# LB_BIT_oX_1IN_1OUT-XL-v03_1_1x.net
KiCad netlist of a schematic drawn in EAGLE
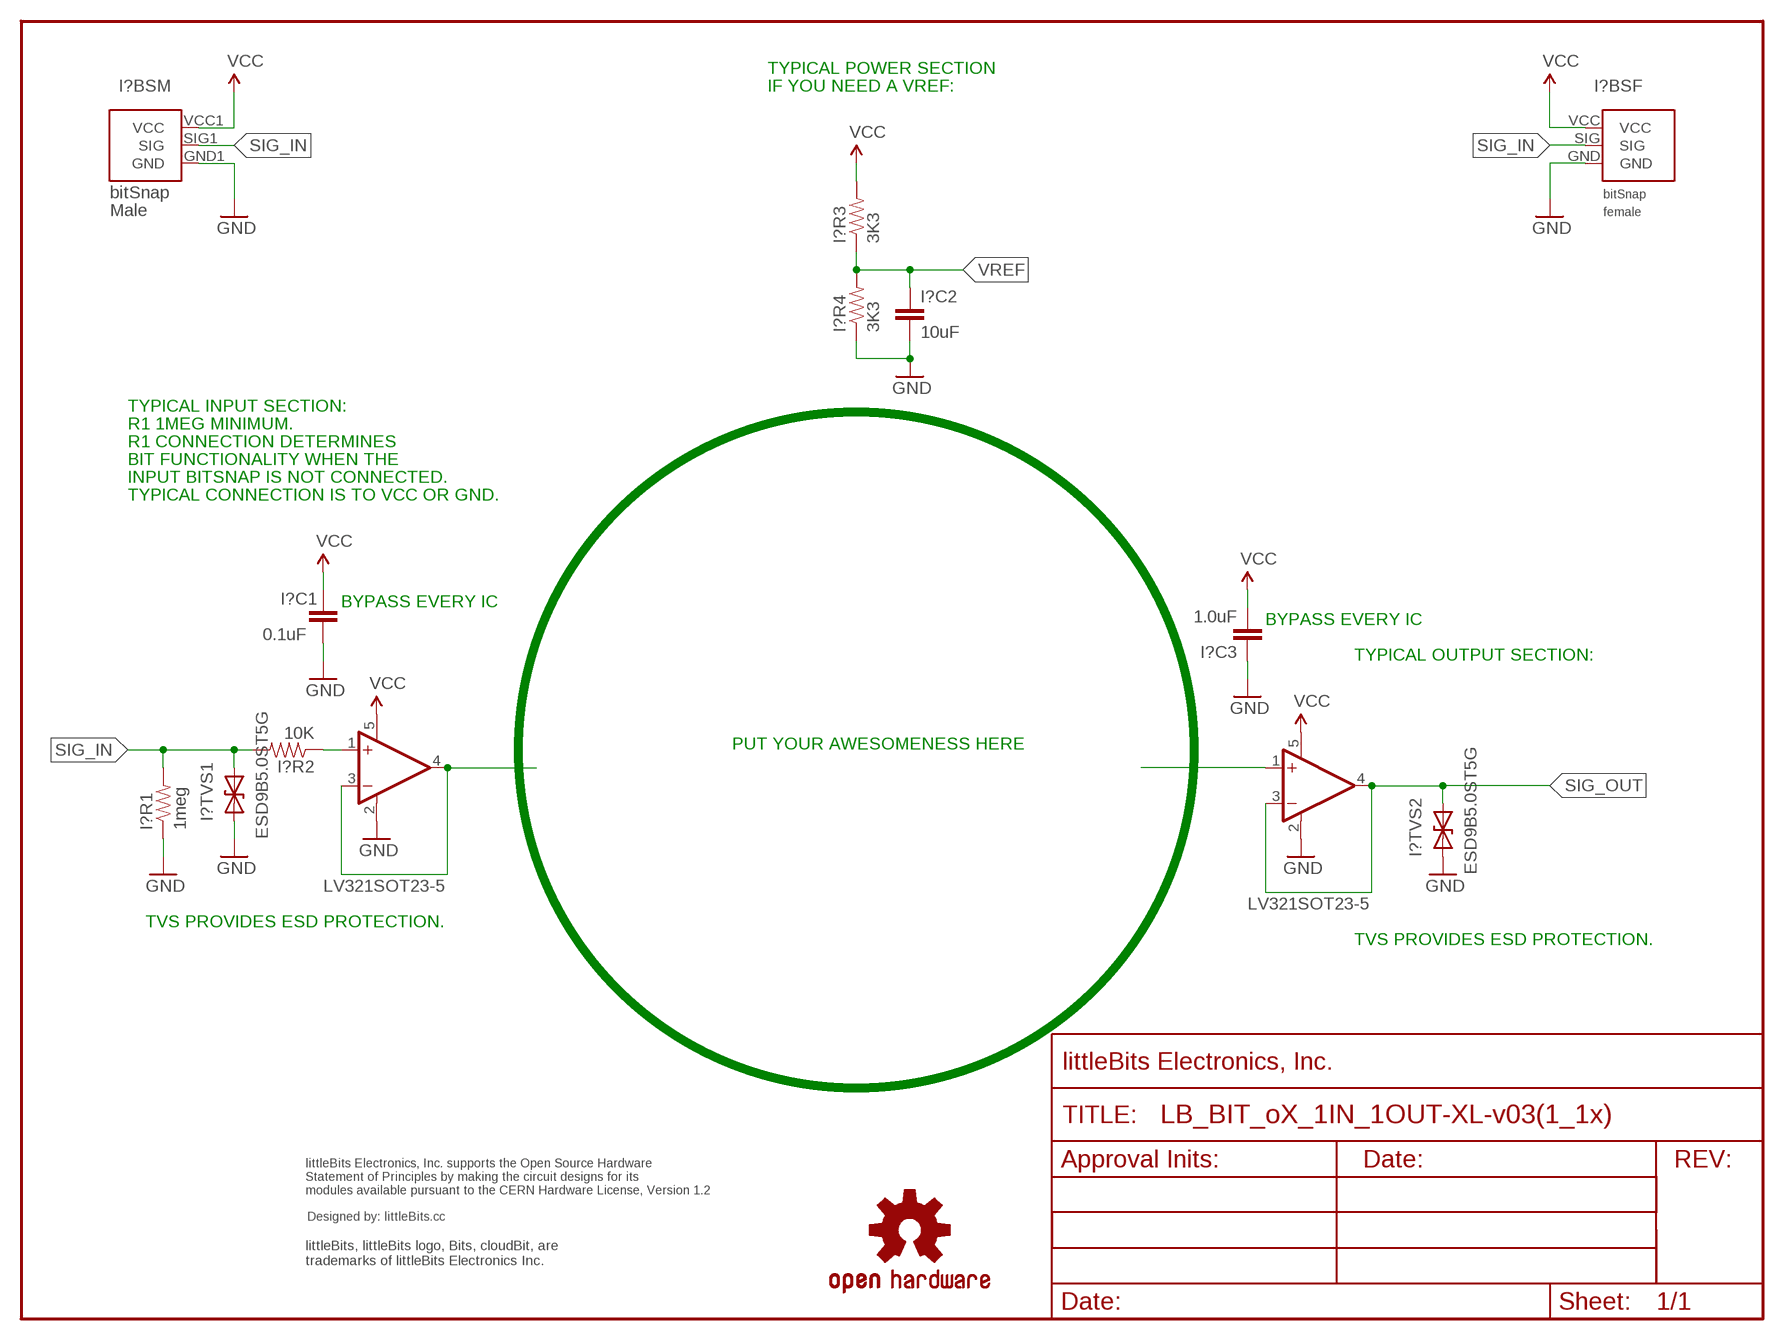
[diagram p0: schematic, sheet 1]

(export (version "E")
  (design (tool "Eeschema 10.0.6"))
  (components
    (comp (ref "I?BSF")
      (value "BITSNAP_V03_FEMALE")
      (footprint "eagle-import:BITSNAP_V03_FEMALE")
      (libsource (lib "eagle-import") (part "BITSNAP_V03_FEMALE"))
    )
    (comp (ref "I?BSM")
      (value "BITSNAP_V03_MALE")
      (footprint "eagle-import:BITSNAP_V03_MALE")
      (libsource (lib "eagle-import") (part "BITSNAP_V03_MALE"))
    )
    (comp (ref "I?C1")
      (value "0.1uF")
      (footprint "eagle-import:CAP-0603")
      (libsource (lib "eagle-import") (part "CAPCAP-0603"))
    )
    (comp (ref "I?C2")
      (value "10uF")
      (footprint "eagle-import:CAP-0603")
      (libsource (lib "eagle-import") (part "CAPCAP-0603"))
    )
    (comp (ref "I?C3")
      (value "1.0uF")
      (footprint "eagle-import:CAP-0603")
      (libsource (lib "eagle-import") (part "CAPCAP-0603"))
    )
    (comp (ref "I?R1")
      (value "1meg")
      (footprint "eagle-import:RES-0603")
      (libsource (lib "eagle-import") (part "RESISTOR0603"))
    )
    (comp (ref "I?R2")
      (value "10K")
      (footprint "eagle-import:RES-0603")
      (libsource (lib "eagle-import") (part "RESISTOR0603"))
    )
    (comp (ref "I?R3")
      (value "3K3")
      (footprint "eagle-import:RES-0603")
      (libsource (lib "eagle-import") (part "RESISTOR0603"))
    )
    (comp (ref "I?R4")
      (value "3K3")
      (footprint "eagle-import:RES-0603")
      (libsource (lib "eagle-import") (part "RESISTOR0603"))
    )
    (comp (ref "I?TVS1")
      (value "ESD9B5.0ST5G")
      (footprint "eagle-import:SOD-923")
      (libsource (lib "eagle-import") (part "DIODE-TVSSOD-923"))
    )
    (comp (ref "I?TVS2")
      (value "ESD9B5.0ST5G")
      (footprint "eagle-import:SOD-923")
      (libsource (lib "eagle-import") (part "DIODE-TVSSOD-923"))
    )
    (comp (ref "U$1")
      (value "FRAME-LETTER")
      (footprint "eagle-import:FABDWG01-OHW")
      (libsource (lib "eagle-import") (part "FRAME-LETTER"))
    )
    (comp (ref "U$2")
      (value "OSHWCREDIT")
      (footprint "eagle-import:OSHWCREDIT")
      (libsource (lib "eagle-import") (part "OSHWCREDIT"))
    )
    (comp (ref "U$3")
      (value "OSHW-LOGOL")
      (footprint "eagle-import:OSHW-LOGO-L")
      (libsource (lib "eagle-import") (part "OSHW-LOGOL"))
    )
    (comp (ref "U1")
      (value "LV321SOT23-5")
      (footprint "eagle-import:SOT23-5")
      (libsource (lib "eagle-import") (part "LV321SOT23-5"))
    )
    (comp (ref "U2")
      (value "LV321SOT23-5")
      (footprint "eagle-import:SOT23-5")
      (libsource (lib "eagle-import") (part "LV321SOT23-5"))
    )
  )
  (nets
    (net (code "1") (name "GND") (class "Default")
      (node (ref "I?BSF") (pin "GND") (pinfunction "GND_GND") (pintype "bidirectional"))
      (node (ref "I?BSM") (pin "GND1") (pinfunction "GND_GND1") (pintype "bidirectional"))
      (node (ref "I?C1") (pin "2") (pinfunction "2_2") (pintype "passive"))
      (node (ref "I?C2") (pin "2") (pinfunction "2_2") (pintype "passive"))
      (node (ref "I?C3") (pin "1") (pinfunction "1_1") (pintype "passive"))
      (node (ref "I?R1") (pin "1") (pinfunction "1_1") (pintype "passive"))
      (node (ref "I?R4") (pin "1") (pinfunction "1_1") (pintype "passive"))
      (node (ref "I?TVS1") (pin "1") (pinfunction "A_1") (pintype "passive"))
      (node (ref "I?TVS2") (pin "1") (pinfunction "A_1") (pintype "passive"))
      (node (ref "U1") (pin "2") (pinfunction "V-_2") (pintype "power_in"))
      (node (ref "U2") (pin "2") (pinfunction "V-_2") (pintype "power_in"))
    )
    (net (code "2") (name "Net-(U1-+IN)") (class "Default")
      (node (ref "I?R2") (pin "1") (pinfunction "1_1") (pintype "passive"))
      (node (ref "U1") (pin "1") (pinfunction "+IN_1") (pintype "input"))
    )
    (net (code "3") (name "Net-(U1--IN)") (class "Default")
      (node (ref "U1") (pin "3") (pinfunction "-IN_3") (pintype "input"))
      (node (ref "U1") (pin "4") (pinfunction "OUT_4") (pintype "output"))
    )
    (net (code "4") (name "SIG_IN") (class "Default")
      (node (ref "I?BSF") (pin "SIG") (pinfunction "SIG_SIG") (pintype "bidirectional"))
      (node (ref "I?BSM") (pin "SIG1") (pinfunction "SIG_SIG1") (pintype "bidirectional"))
      (node (ref "I?R1") (pin "2") (pinfunction "2_2") (pintype "passive"))
      (node (ref "I?R2") (pin "2") (pinfunction "2_2") (pintype "passive"))
      (node (ref "I?TVS1") (pin "2") (pinfunction "C_2") (pintype "passive"))
    )
    (net (code "5") (name "SIG_OUT") (class "Default")
      (node (ref "I?TVS2") (pin "2") (pinfunction "C_2") (pintype "passive"))
      (node (ref "U2") (pin "3") (pinfunction "-IN_3") (pintype "input"))
      (node (ref "U2") (pin "4") (pinfunction "OUT_4") (pintype "output"))
    )
    (net (code "6") (name "VCC") (class "Default")
      (node (ref "I?BSF") (pin "VCC") (pinfunction "VCC_VCC") (pintype "bidirectional"))
      (node (ref "I?BSM") (pin "VCC1") (pinfunction "VCC_VCC1") (pintype "bidirectional"))
      (node (ref "I?C1") (pin "1") (pinfunction "1_1") (pintype "passive"))
      (node (ref "I?C3") (pin "2") (pinfunction "2_2") (pintype "passive"))
      (node (ref "I?R3") (pin "2") (pinfunction "2_2") (pintype "passive"))
      (node (ref "U1") (pin "5") (pinfunction "V+_5") (pintype "power_in"))
      (node (ref "U2") (pin "5") (pinfunction "V+_5") (pintype "power_in"))
    )
    (net (code "7") (name "VREF") (class "Default")
      (node (ref "I?C2") (pin "1") (pinfunction "1_1") (pintype "passive"))
      (node (ref "I?R3") (pin "1") (pinfunction "1_1") (pintype "passive"))
      (node (ref "I?R4") (pin "2") (pinfunction "2_2") (pintype "passive"))
    )
    (net (code "8") (name "unconnected-(U2-+IN-Pad1)") (class "Default")
      (node (ref "U2") (pin "1") (pinfunction "+IN_1") (pintype "input"))
    )
  )
)
